# AMC-SATA.net
KiCad netlist of a schematic drawn in Altium Designer
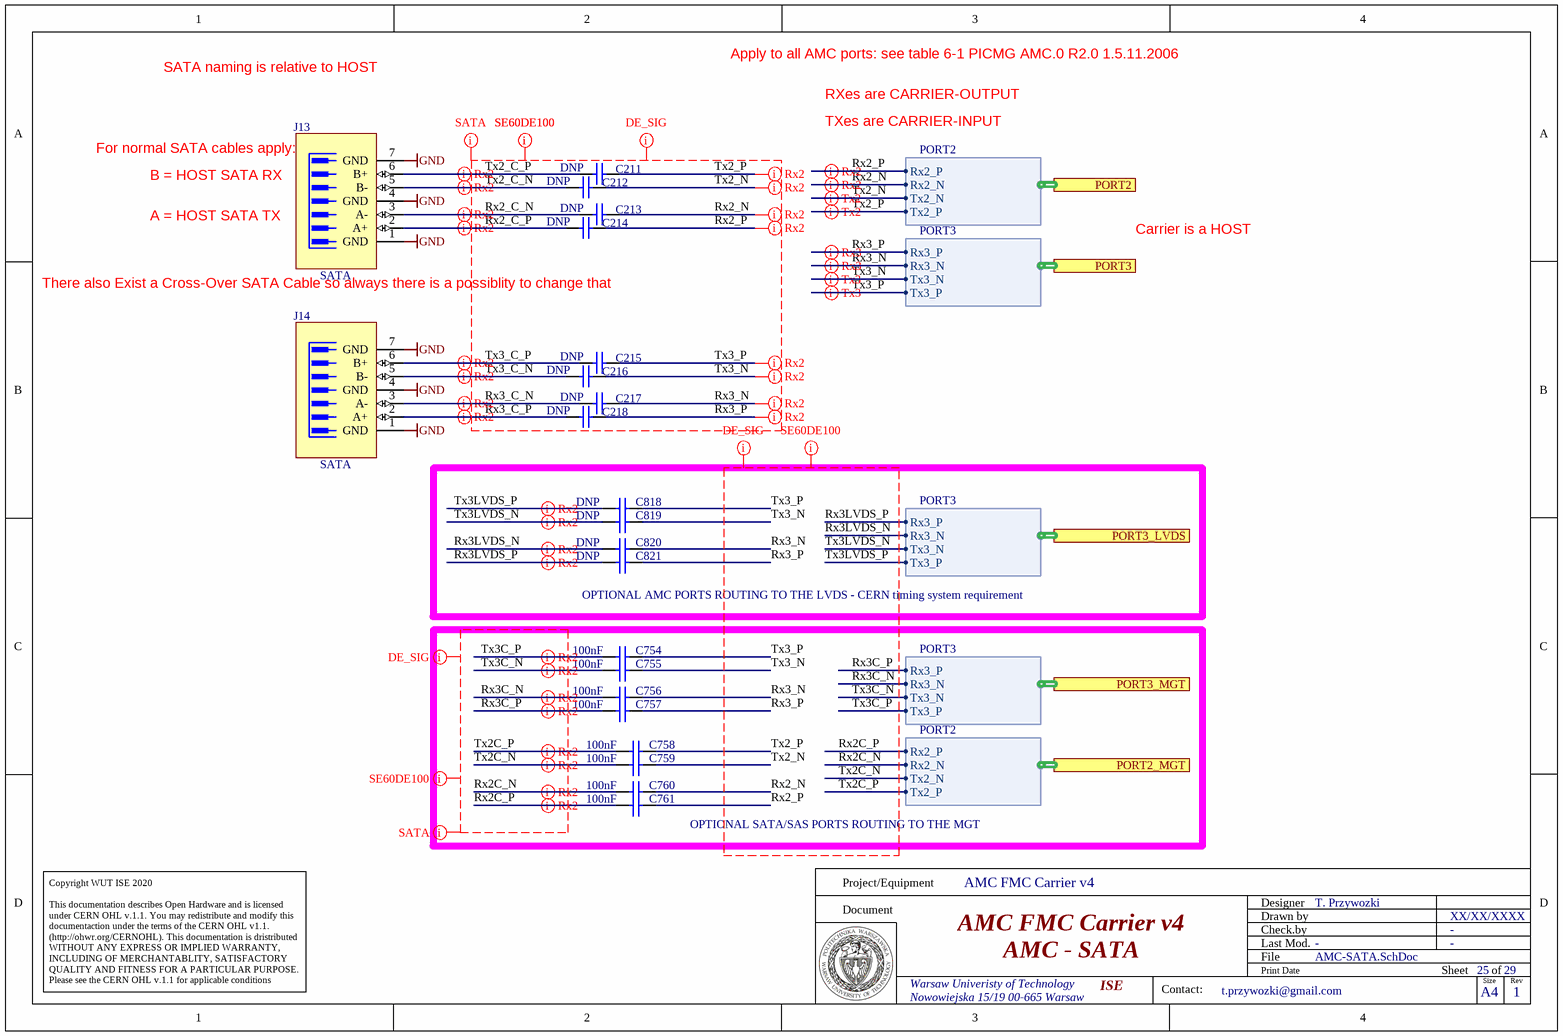
[diagram p0: AMC-SATA.SchDoc]

(export (version "E")
  (design (tool "Eeschema 10.0.6"))
  (components
    (comp (ref "C211")
      (value "DNP")
      (footprint "CAPC0603X33N")
      (description "Non-polarised capacitor")
      (fields
        (field (name "PART NUMBER") "CC0201_100NF_6.3V_10%_X5R")
        (field (name "VOLTAGE") "6.3V")
        (field (name "AUTHOR") "CERN DEM JLC")
      )
      (libsource (lib "Capacitors") (part "Capacitor - non polarized"))
    )
    (comp (ref "C212")
      (value "DNP")
      (footprint "CAPC0603X33N")
      (description "Non-polarised capacitor")
      (fields
        (field (name "PART NUMBER") "CC0201_100NF_6.3V_10%_X5R")
        (field (name "VOLTAGE") "6.3V")
        (field (name "AUTHOR") "CERN DEM JLC")
      )
      (libsource (lib "Capacitors") (part "Capacitor - non polarized"))
    )
    (comp (ref "C213")
      (value "DNP")
      (footprint "CAPC0603X33N")
      (description "Non-polarised capacitor")
      (fields
        (field (name "PART NUMBER") "CC0201_100NF_6.3V_10%_X5R")
        (field (name "VOLTAGE") "6.3V")
        (field (name "AUTHOR") "CERN DEM JLC")
      )
      (libsource (lib "Capacitors") (part "Capacitor - non polarized"))
    )
    (comp (ref "C214")
      (value "DNP")
      (footprint "CAPC0603X33N")
      (description "Non-polarised capacitor")
      (fields
        (field (name "PART NUMBER") "CC0201_100NF_6.3V_10%_X5R")
        (field (name "VOLTAGE") "6.3V")
        (field (name "AUTHOR") "CERN DEM JLC")
      )
      (libsource (lib "Capacitors") (part "Capacitor - non polarized"))
    )
    (comp (ref "C215")
      (value "DNP")
      (footprint "CAPC0603X33N")
      (description "Non-polarised capacitor")
      (fields
        (field (name "PART NUMBER") "CC0201_100NF_6.3V_10%_X5R")
        (field (name "VOLTAGE") "6.3V")
        (field (name "AUTHOR") "CERN DEM JLC")
      )
      (libsource (lib "Capacitors") (part "Capacitor - non polarized"))
    )
    (comp (ref "C216")
      (value "DNP")
      (footprint "CAPC0603X33N")
      (description "Non-polarised capacitor")
      (fields
        (field (name "PART NUMBER") "CC0201_100NF_6.3V_10%_X5R")
        (field (name "VOLTAGE") "6.3V")
        (field (name "AUTHOR") "CERN DEM JLC")
      )
      (libsource (lib "Capacitors") (part "Capacitor - non polarized"))
    )
    (comp (ref "C217")
      (value "DNP")
      (footprint "CAPC0603X33N")
      (description "Non-polarised capacitor")
      (fields
        (field (name "PART NUMBER") "CC0201_100NF_6.3V_10%_X5R")
        (field (name "VOLTAGE") "6.3V")
        (field (name "AUTHOR") "CERN DEM JLC")
      )
      (libsource (lib "Capacitors") (part "Capacitor - non polarized"))
    )
    (comp (ref "C218")
      (value "DNP")
      (footprint "CAPC0603X33N")
      (description "Non-polarised capacitor")
      (fields
        (field (name "PART NUMBER") "CC0201_100NF_6.3V_10%_X5R")
        (field (name "VOLTAGE") "6.3V")
        (field (name "AUTHOR") "CERN DEM JLC")
      )
      (libsource (lib "Capacitors") (part "Capacitor - non polarized"))
    )
    (comp (ref "C754")
      (value "100nF")
      (footprint "CAPC0603X33N")
      (description "Non-polarised capacitor")
      (fields
        (field (name "PART NUMBER") "CC0201_100NF_6.3V_10%_X5R")
        (field (name "VOLTAGE") "6.3V")
        (field (name "AUTHOR") "CERN DEM JLC")
      )
      (libsource (lib "Capacitors") (part "Capacitor - non polarized"))
    )
    (comp (ref "C755")
      (value "100nF")
      (footprint "CAPC0603X33N")
      (description "Non-polarised capacitor")
      (fields
        (field (name "PART NUMBER") "CC0201_100NF_6.3V_10%_X5R")
        (field (name "VOLTAGE") "6.3V")
        (field (name "AUTHOR") "CERN DEM JLC")
      )
      (libsource (lib "Capacitors") (part "Capacitor - non polarized"))
    )
    (comp (ref "C756")
      (value "100nF")
      (footprint "CAPC0603X33N")
      (description "Non-polarised capacitor")
      (fields
        (field (name "PART NUMBER") "CC0201_100NF_6.3V_10%_X5R")
        (field (name "VOLTAGE") "6.3V")
        (field (name "AUTHOR") "CERN DEM JLC")
      )
      (libsource (lib "Capacitors") (part "Capacitor - non polarized"))
    )
    (comp (ref "C757")
      (value "100nF")
      (footprint "CAPC0603X33N")
      (description "Non-polarised capacitor")
      (fields
        (field (name "PART NUMBER") "CC0201_100NF_6.3V_10%_X5R")
        (field (name "VOLTAGE") "6.3V")
        (field (name "AUTHOR") "CERN DEM JLC")
      )
      (libsource (lib "Capacitors") (part "Capacitor - non polarized"))
    )
    (comp (ref "C758")
      (value "100nF")
      (footprint "CAPC0603X33N")
      (description "Non-polarised capacitor")
      (fields
        (field (name "PART NUMBER") "CC0201_100NF_6.3V_10%_X5R")
        (field (name "VOLTAGE") "6.3V")
        (field (name "AUTHOR") "CERN DEM JLC")
      )
      (libsource (lib "Capacitors") (part "Capacitor - non polarized"))
    )
    (comp (ref "C759")
      (value "100nF")
      (footprint "CAPC0603X33N")
      (description "Non-polarised capacitor")
      (fields
        (field (name "PART NUMBER") "CC0201_100NF_6.3V_10%_X5R")
        (field (name "VOLTAGE") "6.3V")
        (field (name "AUTHOR") "CERN DEM JLC")
      )
      (libsource (lib "Capacitors") (part "Capacitor - non polarized"))
    )
    (comp (ref "C760")
      (value "100nF")
      (footprint "CAPC0603X33N")
      (description "Non-polarised capacitor")
      (fields
        (field (name "PART NUMBER") "CC0201_100NF_6.3V_10%_X5R")
        (field (name "VOLTAGE") "6.3V")
        (field (name "AUTHOR") "CERN DEM JLC")
      )
      (libsource (lib "Capacitors") (part "Capacitor - non polarized"))
    )
    (comp (ref "C761")
      (value "100nF")
      (footprint "CAPC0603X33N")
      (description "Non-polarised capacitor")
      (fields
        (field (name "PART NUMBER") "CC0201_100NF_6.3V_10%_X5R")
        (field (name "VOLTAGE") "6.3V")
        (field (name "AUTHOR") "CERN DEM JLC")
      )
      (libsource (lib "Capacitors") (part "Capacitor - non polarized"))
    )
    (comp (ref "C818")
      (value "DNP")
      (footprint "CAPC0603X33N")
      (description "Non-polarised capacitor")
      (fields
        (field (name "PART NUMBER") "CC0201_100NF_6.3V_10%_X5R")
        (field (name "VOLTAGE") "6.3V")
        (field (name "AUTHOR") "CERN DEM JLC")
      )
      (libsource (lib "Capacitors") (part "Capacitor - non polarized"))
    )
    (comp (ref "C819")
      (value "DNP")
      (footprint "CAPC0603X33N")
      (description "Non-polarised capacitor")
      (fields
        (field (name "PART NUMBER") "CC0201_100NF_6.3V_10%_X5R")
        (field (name "VOLTAGE") "6.3V")
        (field (name "AUTHOR") "CERN DEM JLC")
      )
      (libsource (lib "Capacitors") (part "Capacitor - non polarized"))
    )
    (comp (ref "C820")
      (value "DNP")
      (footprint "CAPC0603X33N")
      (description "Non-polarised capacitor")
      (fields
        (field (name "PART NUMBER") "CC0201_100NF_6.3V_10%_X5R")
        (field (name "VOLTAGE") "6.3V")
        (field (name "AUTHOR") "CERN DEM JLC")
      )
      (libsource (lib "Capacitors") (part "Capacitor - non polarized"))
    )
    (comp (ref "C821")
      (value "DNP")
      (footprint "CAPC0603X33N")
      (description "Non-polarised capacitor")
      (fields
        (field (name "PART NUMBER") "CC0201_100NF_6.3V_10%_X5R")
        (field (name "VOLTAGE") "6.3V")
        (field (name "AUTHOR") "CERN DEM JLC")
      )
      (libsource (lib "Capacitors") (part "Capacitor - non polarized"))
    )
    (comp (ref "J13")
      (value "SATA")
      (footprint "MOLEX_67800-5005")
      (description "7 Pin SATA Receptacle")
      (fields
        (field (name "PART NUMBER") "MOLEX_67800-5005")
        (field (name "MANUFACTURER") "MOLEX")
        (field (name "AUTHOR") "CERN DEM MR")
      )
      (libsource (lib "Connectors") (part "Connector SATA 7 Male"))
    )
    (comp (ref "J14")
      (value "SATA")
      (footprint "MOLEX_67800-5005")
      (description "7 Pin SATA Receptacle")
      (fields
        (field (name "PART NUMBER") "MOLEX_67800-5005")
        (field (name "MANUFACTURER") "MOLEX")
        (field (name "AUTHOR") "CERN DEM MR")
      )
      (libsource (lib "Connectors") (part "Connector SATA 7 Male"))
    )
  )
  (nets
    (net (code "3") (name "/Rx2C_N") (class "Default")
      (node (ref "C760") (pin "1") (pinfunction "1_1") (pintype "passive"))
    )
    (net (code "4") (name "/Rx2C_P") (class "Default")
      (node (ref "C761") (pin "1") (pinfunction "1_1") (pintype "passive"))
    )
    (net (code "5") (name "/Rx2_C_N") (class "Default")
      (node (ref "C213") (pin "1") (pinfunction "1_1") (pintype "passive"))
      (node (ref "J13") (pin "3") (pinfunction "A-_3") (pintype "bidirectional"))
    )
    (net (code "6") (name "/Rx2_C_P") (class "Default")
      (node (ref "C214") (pin "1") (pinfunction "1_1") (pintype "passive"))
      (node (ref "J13") (pin "2") (pinfunction "A+_2") (pintype "bidirectional"))
    )
    (net (code "7") (name "/Rx2_N") (class "Default")
      (node (ref "C213") (pin "2") (pinfunction "2_2") (pintype "passive"))
      (node (ref "C760") (pin "2") (pinfunction "2_2") (pintype "passive"))
    )
    (net (code "8") (name "/Rx2_P") (class "Default")
      (node (ref "C214") (pin "2") (pinfunction "2_2") (pintype "passive"))
      (node (ref "C761") (pin "2") (pinfunction "2_2") (pintype "passive"))
    )
    (net (code "9") (name "/Rx3C_N") (class "Default")
      (node (ref "C756") (pin "1") (pinfunction "1_1") (pintype "passive"))
    )
    (net (code "10") (name "/Rx3C_P") (class "Default")
      (node (ref "C757") (pin "1") (pinfunction "1_1") (pintype "passive"))
    )
    (net (code "11") (name "/Rx3LVDS_N") (class "Default")
      (node (ref "C820") (pin "1") (pinfunction "1_1") (pintype "passive"))
    )
    (net (code "12") (name "/Rx3LVDS_P") (class "Default")
      (node (ref "C821") (pin "1") (pinfunction "1_1") (pintype "passive"))
    )
    (net (code "13") (name "/Rx3_C_N") (class "Default")
      (node (ref "C217") (pin "1") (pinfunction "1_1") (pintype "passive"))
      (node (ref "J14") (pin "3") (pinfunction "A-_3") (pintype "bidirectional"))
    )
    (net (code "14") (name "/Rx3_C_P") (class "Default")
      (node (ref "C218") (pin "1") (pinfunction "1_1") (pintype "passive"))
      (node (ref "J14") (pin "2") (pinfunction "A+_2") (pintype "bidirectional"))
    )
    (net (code "15") (name "/Rx3_N") (class "Default")
      (node (ref "C217") (pin "2") (pinfunction "2_2") (pintype "passive"))
      (node (ref "C756") (pin "2") (pinfunction "2_2") (pintype "passive"))
      (node (ref "C820") (pin "2") (pinfunction "2_2") (pintype "passive"))
    )
    (net (code "16") (name "/Rx3_P") (class "Default")
      (node (ref "C218") (pin "2") (pinfunction "2_2") (pintype "passive"))
      (node (ref "C757") (pin "2") (pinfunction "2_2") (pintype "passive"))
      (node (ref "C821") (pin "2") (pinfunction "2_2") (pintype "passive"))
    )
    (net (code "17") (name "/Tx2C_N") (class "Default")
      (node (ref "C759") (pin "1") (pinfunction "1_1") (pintype "passive"))
    )
    (net (code "18") (name "/Tx2C_P") (class "Default")
      (node (ref "C758") (pin "1") (pinfunction "1_1") (pintype "passive"))
    )
    (net (code "19") (name "/Tx2_C_N") (class "Default")
      (node (ref "C212") (pin "1") (pinfunction "1_1") (pintype "passive"))
      (node (ref "J13") (pin "5") (pinfunction "B-_5") (pintype "bidirectional"))
    )
    (net (code "20") (name "/Tx2_C_P") (class "Default")
      (node (ref "C211") (pin "1") (pinfunction "1_1") (pintype "passive"))
      (node (ref "J13") (pin "6") (pinfunction "B+_6") (pintype "bidirectional"))
    )
    (net (code "21") (name "/Tx2_N") (class "Default")
      (node (ref "C212") (pin "2") (pinfunction "2_2") (pintype "passive"))
      (node (ref "C759") (pin "2") (pinfunction "2_2") (pintype "passive"))
    )
    (net (code "22") (name "/Tx2_P") (class "Default")
      (node (ref "C211") (pin "2") (pinfunction "2_2") (pintype "passive"))
      (node (ref "C758") (pin "2") (pinfunction "2_2") (pintype "passive"))
    )
    (net (code "23") (name "/Tx3C_N") (class "Default")
      (node (ref "C755") (pin "1") (pinfunction "1_1") (pintype "passive"))
    )
    (net (code "24") (name "/Tx3C_P") (class "Default")
      (node (ref "C754") (pin "1") (pinfunction "1_1") (pintype "passive"))
    )
    (net (code "25") (name "/Tx3LVDS_N") (class "Default")
      (node (ref "C819") (pin "1") (pinfunction "1_1") (pintype "passive"))
    )
    (net (code "26") (name "/Tx3LVDS_P") (class "Default")
      (node (ref "C818") (pin "1") (pinfunction "1_1") (pintype "passive"))
    )
    (net (code "27") (name "/Tx3_C_N") (class "Default")
      (node (ref "C216") (pin "1") (pinfunction "1_1") (pintype "passive"))
      (node (ref "J14") (pin "5") (pinfunction "B-_5") (pintype "bidirectional"))
    )
    (net (code "28") (name "/Tx3_C_P") (class "Default")
      (node (ref "C215") (pin "1") (pinfunction "1_1") (pintype "passive"))
      (node (ref "J14") (pin "6") (pinfunction "B+_6") (pintype "bidirectional"))
    )
    (net (code "29") (name "/Tx3_N") (class "Default")
      (node (ref "C216") (pin "2") (pinfunction "2_2") (pintype "passive"))
      (node (ref "C755") (pin "2") (pinfunction "2_2") (pintype "passive"))
      (node (ref "C819") (pin "2") (pinfunction "2_2") (pintype "passive"))
    )
    (net (code "30") (name "/Tx3_P") (class "Default")
      (node (ref "C215") (pin "2") (pinfunction "2_2") (pintype "passive"))
      (node (ref "C754") (pin "2") (pinfunction "2_2") (pintype "passive"))
      (node (ref "C818") (pin "2") (pinfunction "2_2") (pintype "passive"))
    )
    (net (code "33") (name "GND") (class "Default")
      (node (ref "J13") (pin "1") (pinfunction "GND_1") (pintype "power_in"))
      (node (ref "J13") (pin "4") (pinfunction "GND_4") (pintype "power_in"))
      (node (ref "J13") (pin "7") (pinfunction "GND_7") (pintype "power_in"))
      (node (ref "J14") (pin "1") (pinfunction "GND_1") (pintype "power_in"))
      (node (ref "J14") (pin "4") (pinfunction "GND_4") (pintype "power_in"))
      (node (ref "J14") (pin "7") (pinfunction "GND_7") (pintype "power_in"))
    )
  )
)
